# wireless_temp_sens.net
KiCad netlist of a schematic drawn in EAGLE
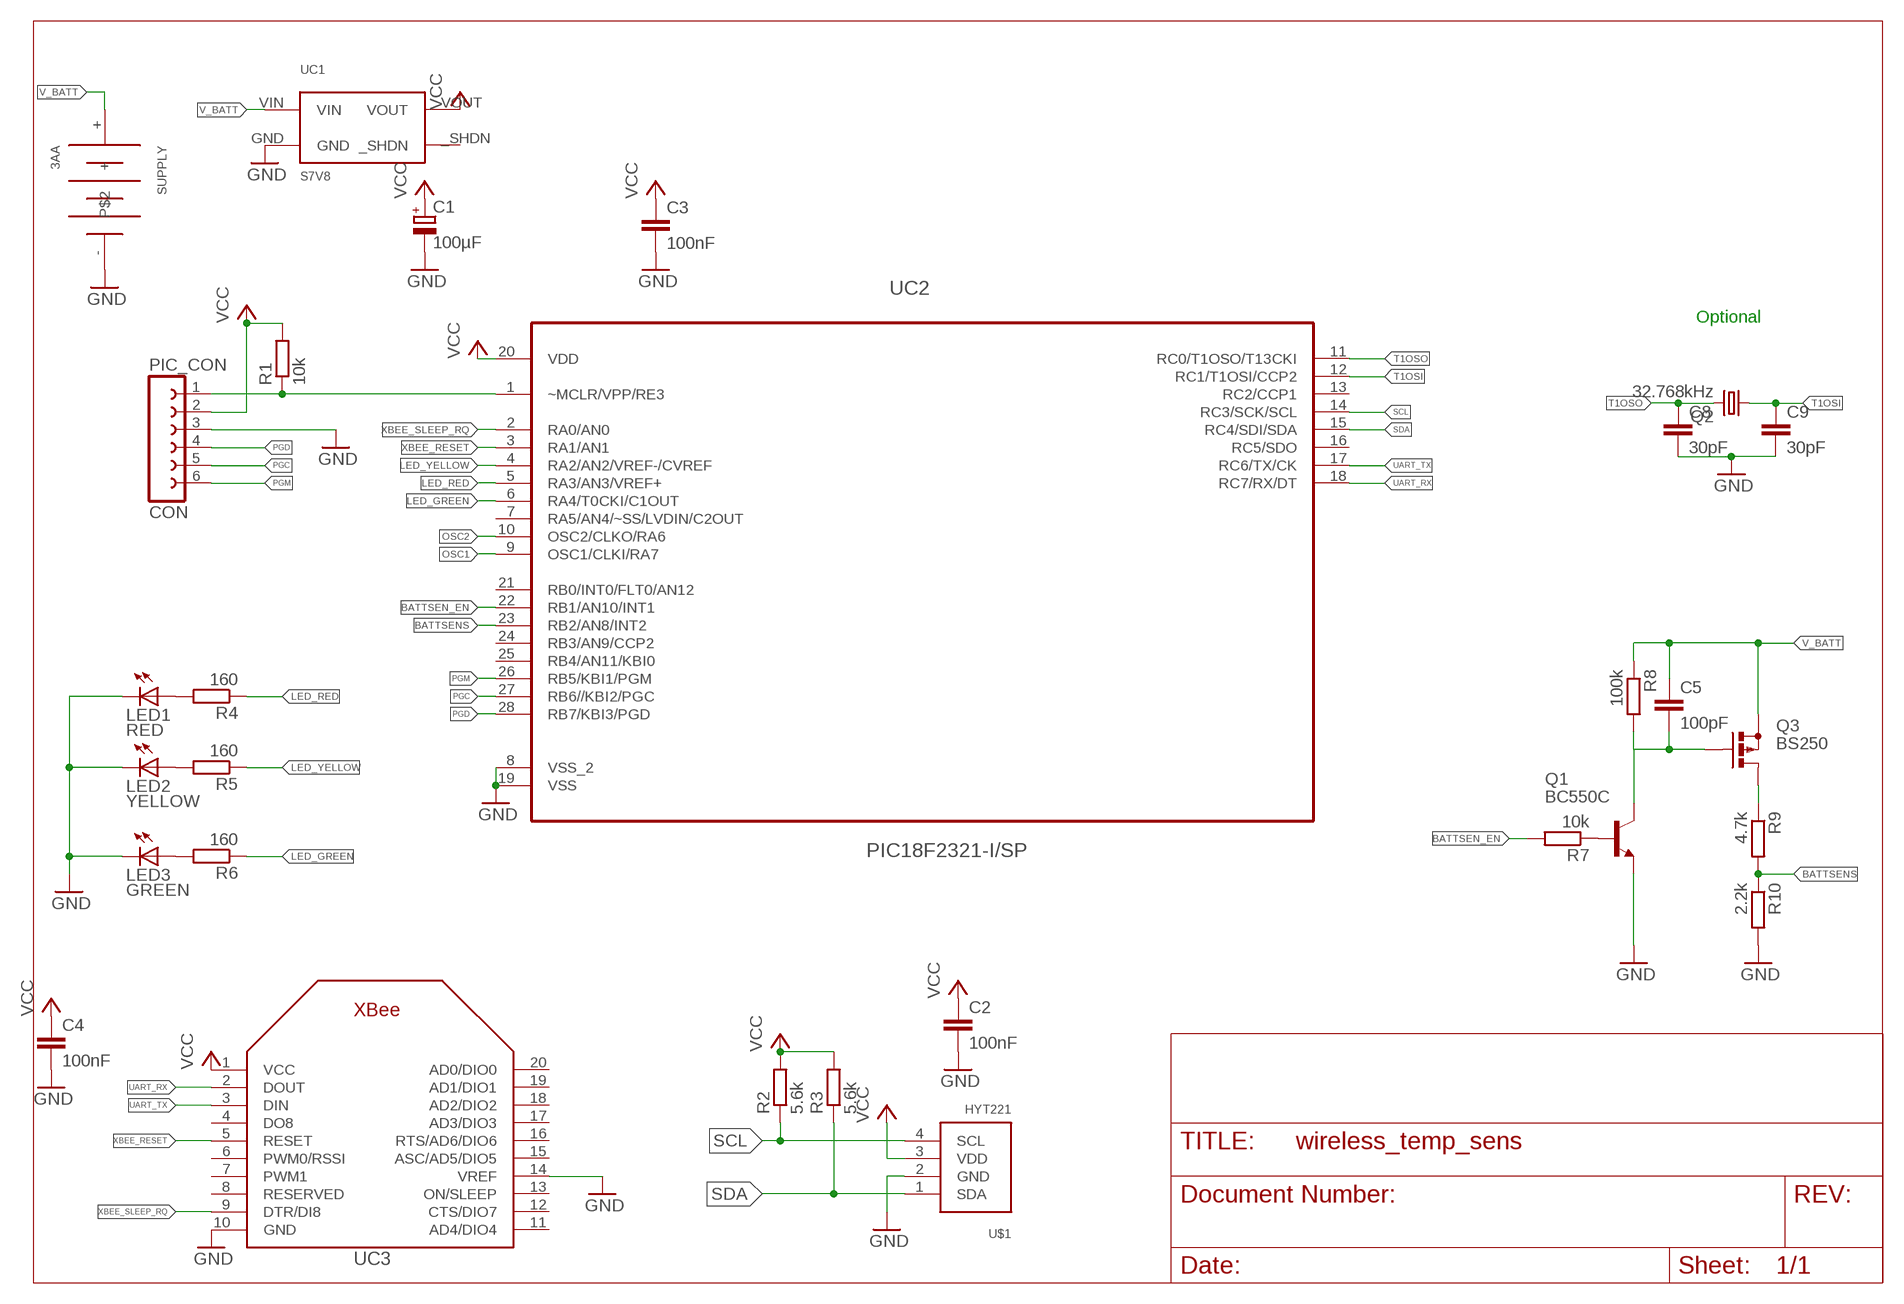
[diagram p0: schematic, sheet 1]

(export (version "E")
  (design (tool "Eeschema 10.0.6"))
  (components
    (comp (ref "C1")
      (value "100µF")
      (footprint "eagle-import:E2,5-6")
      (libsource (lib "eagle-import") (part "CPOL-EUE2.5-6"))
    )
    (comp (ref "C2")
      (value "100nF")
      (footprint "eagle-import:C025-025X050")
      (libsource (lib "eagle-import") (part "C-EU025-025X050"))
    )
    (comp (ref "C3")
      (value "100nF")
      (footprint "eagle-import:C025-025X050")
      (libsource (lib "eagle-import") (part "C-EU025-025X050"))
    )
    (comp (ref "C4")
      (value "100nF")
      (footprint "eagle-import:C025-025X050")
      (libsource (lib "eagle-import") (part "C-EU025-025X050"))
    )
    (comp (ref "C5")
      (value "100pF")
      (footprint "eagle-import:C025-025X050")
      (libsource (lib "eagle-import") (part "C-EU025-025X050"))
    )
    (comp (ref "C8")
      (value "30pF")
      (footprint "eagle-import:C025-024X044")
      (libsource (lib "eagle-import") (part "C-EU025-024X044"))
    )
    (comp (ref "C9")
      (value "30pF")
      (footprint "eagle-import:C025-024X044")
      (libsource (lib "eagle-import") (part "C-EU025-024X044"))
    )
    (comp (ref "CON")
      (value "PIC_CON")
      (footprint "eagle-import:FE06")
      (libsource (lib "eagle-import") (part "FE06-1"))
    )
    (comp (ref "LED1")
      (value "RED")
      (footprint "eagle-import:LED3MM")
      (libsource (lib "eagle-import") (part "LED3MM"))
    )
    (comp (ref "LED2")
      (value "YELLOW")
      (footprint "eagle-import:LED3MM")
      (libsource (lib "eagle-import") (part "LED3MM"))
    )
    (comp (ref "LED3")
      (value "GREEN")
      (footprint "eagle-import:LED3MM")
      (libsource (lib "eagle-import") (part "LED3MM"))
    )
    (comp (ref "Q1")
      (value "BC550C")
      (footprint "eagle-import:TO92-EBC")
      (libsource (lib "eagle-import") (part "BC550C"))
    )
    (comp (ref "Q2")
      (value "32.768kHz")
      (footprint "eagle-import:TC26H")
      (libsource (lib "eagle-import") (part "CRYSTALTC26H"))
    )
    (comp (ref "Q3")
      (value "BS250")
      (footprint "eagle-import:SOT54E")
      (libsource (lib "eagle-import") (part "BS250"))
    )
    (comp (ref "R1")
      (value "10k")
      (footprint "eagle-import:0204_7")
      (libsource (lib "eagle-import") (part "R-EU_0204/7"))
    )
    (comp (ref "R2")
      (value "5.6k")
      (footprint "eagle-import:0204_7")
      (libsource (lib "eagle-import") (part "R-EU_0204/7"))
    )
    (comp (ref "R3")
      (value "5.6k")
      (footprint "eagle-import:0204_7")
      (libsource (lib "eagle-import") (part "R-EU_0204/7"))
    )
    (comp (ref "R4")
      (value "160")
      (footprint "eagle-import:0204_7")
      (libsource (lib "eagle-import") (part "R-EU_0204/7"))
    )
    (comp (ref "R5")
      (value "160")
      (footprint "eagle-import:0204_7")
      (libsource (lib "eagle-import") (part "R-EU_0204/7"))
    )
    (comp (ref "R6")
      (value "160")
      (footprint "eagle-import:0204_7")
      (libsource (lib "eagle-import") (part "R-EU_0204/7"))
    )
    (comp (ref "R7")
      (value "10k")
      (footprint "eagle-import:0204_7")
      (libsource (lib "eagle-import") (part "R-EU_0204/7"))
    )
    (comp (ref "R8")
      (value "100k")
      (footprint "eagle-import:0204_7")
      (libsource (lib "eagle-import") (part "R-EU_0204/7"))
    )
    (comp (ref "R9")
      (value "4.7k")
      (footprint "eagle-import:0204_7")
      (libsource (lib "eagle-import") (part "R-EU_0204/7"))
    )
    (comp (ref "R10")
      (value "2.2k")
      (footprint "eagle-import:0204_7")
      (libsource (lib "eagle-import") (part "R-EU_0204/7"))
    )
    (comp (ref "SUPPLY")
      (value "3AA")
      (footprint "eagle-import:LR6-R6-R6P")
      (libsource (lib "eagle-import") (part "3AA"))
    )
    (comp (ref "U$1")
      (value "HYT221HYT221-CON")
      (footprint "eagle-import:HYT221-CON")
      (libsource (lib "eagle-import") (part "HYT221HYT221-CON"))
    )
    (comp (ref "UC1")
      (value "S7V8")
      (footprint "eagle-import:S7V8_P")
      (libsource (lib "eagle-import") (part "S7V8"))
    )
    (comp (ref "UC2")
      (value "PIC18F2321-I/SP")
      (footprint "eagle-import:DIP254P762X508-28")
      (libsource (lib "eagle-import") (part "PIC18F2321-I/SP"))
    )
    (comp (ref "UC3")
      (value "XBEE")
      (footprint "eagle-import:XBEE")
      (libsource (lib "eagle-import") (part "XBEE"))
    )
  )
  (nets
    (net (code "1") (name "BATTSENS") (class "Default")
      (node (ref "R10") (pin "1") (pinfunction "1_1") (pintype "passive"))
      (node (ref "R9") (pin "2") (pinfunction "2_2") (pintype "passive"))
      (node (ref "UC2") (pin "23") (pinfunction "RB2/AN8/INT2_23") (pintype "bidirectional"))
    )
    (net (code "2") (name "BATTSEN_EN") (class "Default")
      (node (ref "R7") (pin "2") (pinfunction "2_2") (pintype "passive"))
      (node (ref "UC2") (pin "22") (pinfunction "RB1/AN10/INT1_22") (pintype "bidirectional"))
    )
    (net (code "3") (name "GND") (class "Default")
      (node (ref "C1") (pin "-") (pinfunction "-_-") (pintype "passive"))
      (node (ref "C2") (pin "2") (pinfunction "2_2") (pintype "passive"))
      (node (ref "C3") (pin "2") (pinfunction "2_2") (pintype "passive"))
      (node (ref "C4") (pin "2") (pinfunction "2_2") (pintype "passive"))
      (node (ref "C8") (pin "2") (pinfunction "2_2") (pintype "passive"))
      (node (ref "C9") (pin "2") (pinfunction "2_2") (pintype "passive"))
      (node (ref "CON") (pin "3") (pinfunction "3_3") (pintype "passive"))
      (node (ref "LED1") (pin "K") (pinfunction "C_K") (pintype "passive"))
      (node (ref "LED2") (pin "K") (pinfunction "C_K") (pintype "passive"))
      (node (ref "LED3") (pin "K") (pinfunction "C_K") (pintype "passive"))
      (node (ref "Q1") (pin "E") (pinfunction "E_E") (pintype "passive"))
      (node (ref "R10") (pin "2") (pinfunction "2_2") (pintype "passive"))
      (node (ref "SUPPLY") (pin "-") (pinfunction "P$2_-") (pintype "output"))
      (node (ref "U$1") (pin "2") (pinfunction "GND_2") (pintype "power_in"))
      (node (ref "UC1") (pin "GND") (pinfunction "GND_GND") (pintype "bidirectional"))
      (node (ref "UC2") (pin "19") (pinfunction "VSS_19") (pintype "passive"))
      (node (ref "UC2") (pin "8") (pinfunction "VSS_2_8") (pintype "passive"))
      (node (ref "UC3") (pin "10") (pinfunction "GND_10") (pintype "power_in"))
      (node (ref "UC3") (pin "14") (pinfunction "VREF_14") (pintype "input"))
    )
    (net (code "4") (name "LED_GREEN") (class "Default")
      (node (ref "R6") (pin "1") (pinfunction "1_1") (pintype "passive"))
      (node (ref "UC2") (pin "6") (pinfunction "RA4/T0CKI/C1OUT_6") (pintype "bidirectional"))
    )
    (net (code "5") (name "LED_RED") (class "Default")
      (node (ref "R4") (pin "1") (pinfunction "1_1") (pintype "passive"))
      (node (ref "UC2") (pin "5") (pinfunction "RA3/AN3/VREF+_5") (pintype "bidirectional"))
    )
    (net (code "6") (name "LED_YELLOW") (class "Default")
      (node (ref "R5") (pin "1") (pinfunction "1_1") (pintype "passive"))
      (node (ref "UC2") (pin "4") (pinfunction "RA2/AN2/VREF-/CVREF_4") (pintype "bidirectional"))
    )
    (net (code "7") (name "Net-(C5-Pad2)") (class "Default")
      (node (ref "C5") (pin "2") (pinfunction "2_2") (pintype "passive"))
      (node (ref "Q1") (pin "C") (pinfunction "C_C") (pintype "passive"))
      (node (ref "Q3") (pin "G") (pinfunction "G_G") (pintype "passive"))
      (node (ref "R8") (pin "2") (pinfunction "2_2") (pintype "passive"))
    )
    (net (code "8") (name "Net-(LED1-PadA)") (class "Default")
      (node (ref "LED1") (pin "A") (pinfunction "A_A") (pintype "passive"))
      (node (ref "R4") (pin "2") (pinfunction "2_2") (pintype "passive"))
    )
    (net (code "9") (name "Net-(LED2-PadA)") (class "Default")
      (node (ref "LED2") (pin "A") (pinfunction "A_A") (pintype "passive"))
      (node (ref "R5") (pin "2") (pinfunction "2_2") (pintype "passive"))
    )
    (net (code "10") (name "Net-(LED3-PadA)") (class "Default")
      (node (ref "LED3") (pin "A") (pinfunction "A_A") (pintype "passive"))
      (node (ref "R6") (pin "2") (pinfunction "2_2") (pintype "passive"))
    )
    (net (code "11") (name "Net-(Q1-PadB)") (class "Default")
      (node (ref "Q1") (pin "B") (pinfunction "B_B") (pintype "passive"))
      (node (ref "R7") (pin "1") (pinfunction "1_1") (pintype "passive"))
    )
    (net (code "12") (name "Net-(Q3-PadD)") (class "Default")
      (node (ref "Q3") (pin "D") (pinfunction "D_D") (pintype "passive"))
      (node (ref "R9") (pin "1") (pinfunction "1_1") (pintype "passive"))
    )
    (net (code "13") (name "Net-(UC2-~{MCLR{slash}VPP{slash}RE3})") (class "Default")
      (node (ref "CON") (pin "1") (pinfunction "1_1") (pintype "passive"))
      (node (ref "R1") (pin "1") (pinfunction "1_1") (pintype "passive"))
      (node (ref "UC2") (pin "1") (pinfunction "~{MCLR/VPP/RE3}_1") (pintype "input"))
    )
    (net (code "14") (name "OSC1") (class "Default")
      (node (ref "UC2") (pin "9") (pinfunction "OSC1/CLKI/RA7_9") (pintype "bidirectional"))
    )
    (net (code "15") (name "OSC2") (class "Default")
      (node (ref "UC2") (pin "10") (pinfunction "OSC2/CLKO/RA6_10") (pintype "bidirectional"))
    )
    (net (code "16") (name "PGC") (class "Default")
      (node (ref "CON") (pin "5") (pinfunction "5_5") (pintype "passive"))
      (node (ref "UC2") (pin "27") (pinfunction "RB6//KBI2/PGC_27") (pintype "bidirectional"))
    )
    (net (code "17") (name "PGD") (class "Default")
      (node (ref "CON") (pin "4") (pinfunction "4_4") (pintype "passive"))
      (node (ref "UC2") (pin "28") (pinfunction "RB7/KBI3/PGD_28") (pintype "bidirectional"))
    )
    (net (code "18") (name "PGM") (class "Default")
      (node (ref "CON") (pin "6") (pinfunction "6_6") (pintype "passive"))
      (node (ref "UC2") (pin "26") (pinfunction "RB5/KBI1/PGM_26") (pintype "bidirectional"))
    )
    (net (code "19") (name "SCL") (class "Default")
      (node (ref "R2") (pin "1") (pinfunction "1_1") (pintype "passive"))
      (node (ref "U$1") (pin "4") (pinfunction "SCL_4") (pintype "input"))
      (node (ref "UC2") (pin "14") (pinfunction "RC3/SCK/SCL_14") (pintype "bidirectional"))
    )
    (net (code "20") (name "SDA") (class "Default")
      (node (ref "R3") (pin "1") (pinfunction "1_1") (pintype "passive"))
      (node (ref "U$1") (pin "1") (pinfunction "SDA_1") (pintype "bidirectional"))
      (node (ref "UC2") (pin "15") (pinfunction "RC4/SDI/SDA_15") (pintype "bidirectional"))
    )
    (net (code "21") (name "T1OSI") (class "Default")
      (node (ref "C9") (pin "1") (pinfunction "1_1") (pintype "passive"))
      (node (ref "Q2") (pin "1") (pinfunction "1_1") (pintype "passive"))
      (node (ref "UC2") (pin "12") (pinfunction "RC1/T1OSI/CCP2_12") (pintype "bidirectional"))
    )
    (net (code "22") (name "T1OSO") (class "Default")
      (node (ref "C8") (pin "1") (pinfunction "1_1") (pintype "passive"))
      (node (ref "Q2") (pin "2") (pinfunction "2_2") (pintype "passive"))
      (node (ref "UC2") (pin "11") (pinfunction "RC0/T1OSO/T13CKI_11") (pintype "bidirectional"))
    )
    (net (code "23") (name "UART_RX") (class "Default")
      (node (ref "UC2") (pin "18") (pinfunction "RC7/RX/DT_18") (pintype "bidirectional"))
      (node (ref "UC3") (pin "2") (pinfunction "DOUT_2") (pintype "output"))
    )
    (net (code "24") (name "UART_TX") (class "Default")
      (node (ref "UC2") (pin "17") (pinfunction "RC6/TX/CK_17") (pintype "bidirectional"))
      (node (ref "UC3") (pin "3") (pinfunction "DIN_3") (pintype "input"))
    )
    (net (code "25") (name "VCC") (class "Default")
      (node (ref "C1") (pin "+") (pinfunction "+_+") (pintype "passive"))
      (node (ref "C2") (pin "1") (pinfunction "1_1") (pintype "passive"))
      (node (ref "C3") (pin "1") (pinfunction "1_1") (pintype "passive"))
      (node (ref "C4") (pin "1") (pinfunction "1_1") (pintype "passive"))
      (node (ref "CON") (pin "2") (pinfunction "2_2") (pintype "passive"))
      (node (ref "R1") (pin "2") (pinfunction "2_2") (pintype "passive"))
      (node (ref "R2") (pin "2") (pinfunction "2_2") (pintype "passive"))
      (node (ref "R3") (pin "2") (pinfunction "2_2") (pintype "passive"))
      (node (ref "U$1") (pin "3") (pinfunction "VDD_3") (pintype "power_in"))
      (node (ref "UC1") (pin "VOUT") (pinfunction "VOUT_VOUT") (pintype "power_in"))
      (node (ref "UC2") (pin "20") (pinfunction "VDD_20") (pintype "power_in"))
      (node (ref "UC3") (pin "1") (pinfunction "VCC_1") (pintype "power_in"))
    )
    (net (code "26") (name "V_BATT") (class "Default")
      (node (ref "C5") (pin "1") (pinfunction "1_1") (pintype "passive"))
      (node (ref "Q3") (pin "S") (pinfunction "S_S") (pintype "passive"))
      (node (ref "R8") (pin "1") (pinfunction "1_1") (pintype "passive"))
      (node (ref "SUPPLY") (pin "+") (pinfunction "+_+") (pintype "output"))
      (node (ref "UC1") (pin "VIN") (pinfunction "VIN_VIN") (pintype "input"))
    )
    (net (code "27") (name "XBEE_RESET") (class "Default")
      (node (ref "UC2") (pin "3") (pinfunction "RA1/AN1_3") (pintype "bidirectional"))
      (node (ref "UC3") (pin "5") (pinfunction "RESET_5") (pintype "input"))
    )
    (net (code "28") (name "XBEE_SLEEP_RQ") (class "Default")
      (node (ref "UC2") (pin "2") (pinfunction "RA0/AN0_2") (pintype "bidirectional"))
      (node (ref "UC3") (pin "9") (pinfunction "DTR/DI8_9") (pintype "input"))
    )
    (net (code "29") (name "unconnected-(UC1-Pad_SHDN)") (class "Default")
      (node (ref "UC1") (pin "_SHDN") (pinfunction "_SHDN__SHDN") (pintype "output"))
    )
    (net (code "30") (name "unconnected-(UC2-RA5{slash}AN4{slash}~{SS{slash}LVDIN{slash}C2OUT}-Pad7)") (class "Default")
      (node (ref "UC2") (pin "7") (pinfunction "RA5/AN4/~{SS/LVDIN/C2OUT}_7") (pintype "bidirectional"))
    )
    (net (code "31") (name "unconnected-(UC2-RB0{slash}INT0{slash}FLT0{slash}AN12-Pad21)") (class "Default")
      (node (ref "UC2") (pin "21") (pinfunction "RB0/INT0/FLT0/AN12_21") (pintype "bidirectional"))
    )
    (net (code "32") (name "unconnected-(UC2-RB3{slash}AN9{slash}CCP2-Pad24)") (class "Default")
      (node (ref "UC2") (pin "24") (pinfunction "RB3/AN9/CCP2_24") (pintype "bidirectional"))
    )
    (net (code "33") (name "unconnected-(UC2-RB4{slash}AN11{slash}KBI0-Pad25)") (class "Default")
      (node (ref "UC2") (pin "25") (pinfunction "RB4/AN11/KBI0_25") (pintype "bidirectional"))
    )
    (net (code "34") (name "unconnected-(UC2-RC2{slash}CCP1-Pad13)") (class "Default")
      (node (ref "UC2") (pin "13") (pinfunction "RC2/CCP1_13") (pintype "bidirectional"))
    )
    (net (code "35") (name "unconnected-(UC2-RC5{slash}SDO-Pad16)") (class "Default")
      (node (ref "UC2") (pin "16") (pinfunction "RC5/SDO_16") (pintype "bidirectional"))
    )
    (net (code "36") (name "unconnected-(UC3-AD0{slash}DIO0-Pad20)") (class "Default")
      (node (ref "UC3") (pin "20") (pinfunction "AD0/DIO0_20") (pintype "bidirectional"))
    )
    (net (code "37") (name "unconnected-(UC3-AD1{slash}DIO1-Pad19)") (class "Default")
      (node (ref "UC3") (pin "19") (pinfunction "AD1/DIO1_19") (pintype "bidirectional"))
    )
    (net (code "38") (name "unconnected-(UC3-AD2{slash}DIO2-Pad18)") (class "Default")
      (node (ref "UC3") (pin "18") (pinfunction "AD2/DIO2_18") (pintype "bidirectional"))
    )
    (net (code "39") (name "unconnected-(UC3-AD3{slash}DIO3-Pad17)") (class "Default")
      (node (ref "UC3") (pin "17") (pinfunction "AD3/DIO3_17") (pintype "bidirectional"))
    )
    (net (code "40") (name "unconnected-(UC3-AD4{slash}DIO4-Pad11)") (class "Default")
      (node (ref "UC3") (pin "11") (pinfunction "AD4/DIO4_11") (pintype "bidirectional"))
    )
    (net (code "41") (name "unconnected-(UC3-ASC{slash}AD5{slash}DIO5-Pad15)") (class "Default")
      (node (ref "UC3") (pin "15") (pinfunction "ASC/AD5/DIO5_15") (pintype "bidirectional"))
    )
    (net (code "42") (name "unconnected-(UC3-CTS{slash}DIO7-Pad12)") (class "Default")
      (node (ref "UC3") (pin "12") (pinfunction "CTS/DIO7_12") (pintype "bidirectional"))
    )
    (net (code "43") (name "unconnected-(UC3-DO8-Pad4)") (class "Default")
      (node (ref "UC3") (pin "4") (pinfunction "DO8_4") (pintype "output"))
    )
    (net (code "44") (name "unconnected-(UC3-ON{slash}SLEEP-Pad13)") (class "Default")
      (node (ref "UC3") (pin "13") (pinfunction "ON/SLEEP_13") (pintype "output"))
    )
    (net (code "45") (name "unconnected-(UC3-PWM0{slash}RSSI-Pad6)") (class "Default")
      (node (ref "UC3") (pin "6") (pinfunction "PWM0/RSSI_6") (pintype "output"))
    )
    (net (code "46") (name "unconnected-(UC3-PWM1-Pad7)") (class "Default")
      (node (ref "UC3") (pin "7") (pinfunction "PWM1_7") (pintype "output"))
    )
    (net (code "47") (name "unconnected-(UC3-RESERVED-Pad8)") (class "Default")
      (node (ref "UC3") (pin "8") (pinfunction "RESERVED_8") (pintype "no_connect"))
    )
    (net (code "48") (name "unconnected-(UC3-RTS{slash}AD6{slash}DIO6-Pad16)") (class "Default")
      (node (ref "UC3") (pin "16") (pinfunction "RTS/AD6/DIO6_16") (pintype "bidirectional"))
    )
  )
)
